# eth.net
KiCad netlist of a schematic drawn in Altium Designer
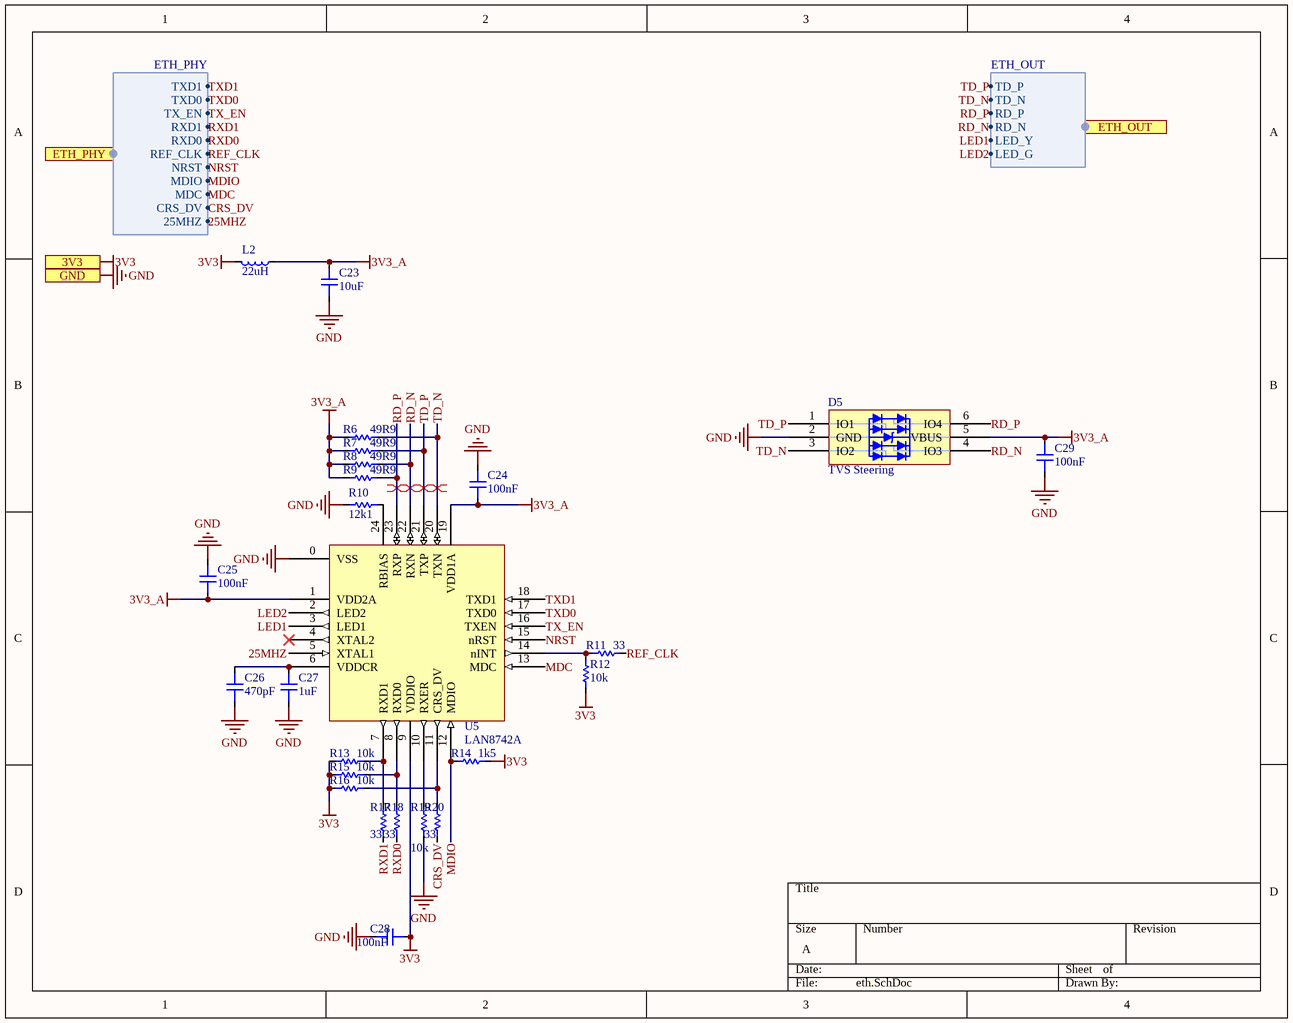
[diagram p0: eth.SchDoc]

(export (version "E")
  (design (tool "Eeschema 10.0.6"))
  (components
    (comp (ref "C23")
      (value "10uF")
      (footprint "CAP 0805 L")
      (description "CAP 0805")
      (libsource (lib "streetbot") (part "CAP 0805"))
    )
    (comp (ref "C24")
      (value "100nF")
      (footprint "CAP 0805 L")
      (description "CAP 0805")
      (libsource (lib "streetbot") (part "CAP 0805"))
    )
    (comp (ref "C25")
      (value "100nF")
      (footprint "CAP 0805 L")
      (description "CAP 0805")
      (libsource (lib "streetbot") (part "CAP 0805"))
    )
    (comp (ref "C26")
      (value "470pF")
      (footprint "CAP 0805 L")
      (description "CAP 0805")
      (libsource (lib "streetbot") (part "CAP 0805"))
    )
    (comp (ref "C27")
      (value "1uF")
      (footprint "CAP 0805 L")
      (description "CAP 0805")
      (libsource (lib "streetbot") (part "CAP 0805"))
    )
    (comp (ref "C28")
      (value "100nF")
      (footprint "CAP 0805 L")
      (description "CAP 0805")
      (libsource (lib "streetbot") (part "CAP 0805"))
    )
    (comp (ref "C29")
      (value "100nF")
      (footprint "CAP 0805 L")
      (description "CAP 0805")
      (libsource (lib "streetbot") (part "CAP 0805"))
    )
    (comp (ref "D5")
      (value "TVS Steering")
      (footprint "SC-74")
      (description "CM1293A-04SO")
      (libsource (lib "streetbot") (part "DTVS 2Rail 4x"))
    )
    (comp (ref "L2")
      (value "22uH")
      (footprint "IND 0805 L")
      (description "IND 0805")
      (libsource (lib "streetbot") (part "IND 0805"))
    )
    (comp (ref "R6")
      (value "49R9")
      (footprint "RES 0603 L")
      (description "RES 0603")
      (libsource (lib "streetbot") (part "RES 0603"))
    )
    (comp (ref "R7")
      (value "49R9")
      (footprint "RES 0603 L")
      (description "RES 0603")
      (libsource (lib "streetbot") (part "RES 0603"))
    )
    (comp (ref "R8")
      (value "49R9")
      (footprint "RES 0603 L")
      (description "RES 0603")
      (libsource (lib "streetbot") (part "RES 0603"))
    )
    (comp (ref "R9")
      (value "49R9")
      (footprint "RES 0603 L")
      (description "RES 0603")
      (libsource (lib "streetbot") (part "RES 0603"))
    )
    (comp (ref "R10")
      (value "12k1")
      (footprint "RES 0603 L")
      (description "RES 0603")
      (libsource (lib "streetbot") (part "RES 0603"))
    )
    (comp (ref "R11")
      (value "33")
      (footprint "RES 0603 L")
      (description "RES 0603")
      (libsource (lib "streetbot") (part "RES 0603"))
    )
    (comp (ref "R12")
      (value "10k")
      (footprint "RES 0603 L")
      (description "RES 0603")
      (libsource (lib "streetbot") (part "RES 0603"))
    )
    (comp (ref "R13")
      (value "10k")
      (footprint "RES 0603 L")
      (description "RES 0603")
      (libsource (lib "streetbot") (part "RES 0603"))
    )
    (comp (ref "R14")
      (value "1k5")
      (footprint "RES 0603 L")
      (description "RES 0603")
      (libsource (lib "streetbot") (part "RES 0603"))
    )
    (comp (ref "R15")
      (value "10k")
      (footprint "RES 0603 L")
      (description "RES 0603")
      (libsource (lib "streetbot") (part "RES 0603"))
    )
    (comp (ref "R16")
      (value "10k")
      (footprint "RES 0603 L")
      (description "RES 0603")
      (libsource (lib "streetbot") (part "RES 0603"))
    )
    (comp (ref "R17")
      (value "33")
      (footprint "RES 0603 L")
      (description "RES 0603")
      (libsource (lib "streetbot") (part "RES 0603"))
    )
    (comp (ref "R18")
      (value "33")
      (footprint "RES 0603 L")
      (description "RES 0603")
      (libsource (lib "streetbot") (part "RES 0603"))
    )
    (comp (ref "R19")
      (value "10k")
      (footprint "RES 0603 L")
      (description "RES 0603")
      (libsource (lib "streetbot") (part "RES 0603"))
    )
    (comp (ref "R20")
      (value "33")
      (footprint "RES 0603 L")
      (description "RES 0603")
      (libsource (lib "streetbot") (part "RES 0603"))
    )
    (comp (ref "U5")
      (value "LAN8742A")
      (footprint "VQFN24")
      (description "LAN8742A-CZ-TR\r\nLAN8742AI-CZ-TR")
      (libsource (lib "streetbot") (part "IC ETH PHY RMII"))
    )
  )
  (nets
    (net (code "3") (name "/25MHZ") (class "Default")
      (node (ref "U5") (pin "5") (pinfunction "XTAL1_5") (pintype "input"))
    )
    (net (code "4") (name "/CRS_DV") (class "Default")
      (node (ref "R20") (pin "1") (pinfunction "1_1") (pintype "passive"))
    )
    (net (code "5") (name "/LED1") (class "Default")
      (node (ref "U5") (pin "3") (pinfunction "LED1_3") (pintype "output"))
    )
    (net (code "6") (name "/LED2") (class "Default")
      (node (ref "U5") (pin "2") (pinfunction "LED2_2") (pintype "output"))
    )
    (net (code "7") (name "/MDC") (class "Default")
      (node (ref "U5") (pin "13") (pinfunction "MDC_13") (pintype "input"))
    )
    (net (code "8") (name "/MDIO") (class "Default")
      (node (ref "R14") (pin "2") (pinfunction "2_2") (pintype "passive"))
      (node (ref "U5") (pin "12") (pinfunction "MDIO_12") (pintype "input"))
    )
    (net (code "9") (name "/NRST") (class "Default")
      (node (ref "U5") (pin "15") (pinfunction "nRST_15") (pintype "input"))
    )
    (net (code "10") (name "/RD_N") (class "Default")
      (node (ref "D5") (pin "4") (pinfunction "IO3_4") (pintype "passive"))
      (node (ref "R8") (pin "1") (pinfunction "1_1") (pintype "passive"))
      (node (ref "U5") (pin "22") (pinfunction "RXN_22") (pintype "bidirectional"))
    )
    (net (code "11") (name "/RD_P") (class "Default")
      (node (ref "D5") (pin "6") (pinfunction "IO4_6") (pintype "passive"))
      (node (ref "R9") (pin "1") (pinfunction "1_1") (pintype "passive"))
      (node (ref "U5") (pin "23") (pinfunction "RXP_23") (pintype "bidirectional"))
    )
    (net (code "12") (name "/REF_CLK") (class "Default")
      (node (ref "R11") (pin "1") (pinfunction "1_1") (pintype "passive"))
    )
    (net (code "13") (name "/RXD0") (class "Default")
      (node (ref "R18") (pin "1") (pinfunction "1_1") (pintype "passive"))
    )
    (net (code "14") (name "/RXD1") (class "Default")
      (node (ref "R17") (pin "1") (pinfunction "1_1") (pintype "passive"))
    )
    (net (code "15") (name "/TD_N") (class "Default")
      (node (ref "D5") (pin "3") (pinfunction "IO2_3") (pintype "passive"))
      (node (ref "R6") (pin "1") (pinfunction "1_1") (pintype "passive"))
      (node (ref "U5") (pin "20") (pinfunction "TXN_20") (pintype "bidirectional"))
    )
    (net (code "16") (name "/TD_P") (class "Default")
      (node (ref "D5") (pin "1") (pinfunction "IO1_1") (pintype "passive"))
      (node (ref "R7") (pin "1") (pinfunction "1_1") (pintype "passive"))
      (node (ref "U5") (pin "21") (pinfunction "TXP_21") (pintype "bidirectional"))
    )
    (net (code "17") (name "/TXD0") (class "Default")
      (node (ref "U5") (pin "17") (pinfunction "TXD0_17") (pintype "input"))
    )
    (net (code "18") (name "/TXD1") (class "Default")
      (node (ref "U5") (pin "18") (pinfunction "TXD1_18") (pintype "input"))
    )
    (net (code "19") (name "/TX_EN") (class "Default")
      (node (ref "U5") (pin "16") (pinfunction "TXEN_16") (pintype "input"))
    )
    (net (code "22") (name "3V3") (class "Default")
      (node (ref "C28") (pin "2") (pinfunction "2_2") (pintype "passive"))
      (node (ref "L2") (pin "2") (pinfunction "2_2") (pintype "passive"))
      (node (ref "R12") (pin "2") (pinfunction "2_2") (pintype "passive"))
      (node (ref "R13") (pin "2") (pinfunction "2_2") (pintype "passive"))
      (node (ref "R14") (pin "1") (pinfunction "1_1") (pintype "passive"))
      (node (ref "R15") (pin "2") (pinfunction "2_2") (pintype "passive"))
      (node (ref "R16") (pin "2") (pinfunction "2_2") (pintype "passive"))
      (node (ref "U5") (pin "9") (pinfunction "VDDIO_9") (pintype "power_in"))
    )
    (net (code "23") (name "3V3_A") (class "Default")
      (node (ref "C23") (pin "2") (pinfunction "2_2") (pintype "passive"))
      (node (ref "C24") (pin "1") (pinfunction "1_1") (pintype "passive"))
      (node (ref "C25") (pin "1") (pinfunction "1_1") (pintype "passive"))
      (node (ref "C29") (pin "2") (pinfunction "2_2") (pintype "passive"))
      (node (ref "D5") (pin "5") (pinfunction "VBUS_5") (pintype "passive"))
      (node (ref "L2") (pin "1") (pinfunction "1_1") (pintype "passive"))
      (node (ref "R6") (pin "2") (pinfunction "2_2") (pintype "passive"))
      (node (ref "R7") (pin "2") (pinfunction "2_2") (pintype "passive"))
      (node (ref "R8") (pin "2") (pinfunction "2_2") (pintype "passive"))
      (node (ref "R9") (pin "2") (pinfunction "2_2") (pintype "passive"))
      (node (ref "U5") (pin "1") (pinfunction "VDD2A_1") (pintype "power_in"))
      (node (ref "U5") (pin "19") (pinfunction "VDD1A_19") (pintype "power_in"))
    )
    (net (code "24") (name "GND") (class "Default")
      (node (ref "C23") (pin "1") (pinfunction "1_1") (pintype "passive"))
      (node (ref "C24") (pin "2") (pinfunction "2_2") (pintype "passive"))
      (node (ref "C25") (pin "2") (pinfunction "2_2") (pintype "passive"))
      (node (ref "C26") (pin "1") (pinfunction "1_1") (pintype "passive"))
      (node (ref "C27") (pin "1") (pinfunction "1_1") (pintype "passive"))
      (node (ref "C28") (pin "1") (pinfunction "1_1") (pintype "passive"))
      (node (ref "C29") (pin "1") (pinfunction "1_1") (pintype "passive"))
      (node (ref "D5") (pin "2") (pinfunction "GND_2") (pintype "passive"))
      (node (ref "R10") (pin "1") (pinfunction "1_1") (pintype "passive"))
      (node (ref "R19") (pin "1") (pinfunction "1_1") (pintype "passive"))
      (node (ref "U5") (pin "0") (pinfunction "VSS_0") (pintype "power_in"))
    )
    (net (code "25") (name "Net-(U5-CRS_DV)") (class "Default")
      (node (ref "R16") (pin "1") (pinfunction "1_1") (pintype "passive"))
      (node (ref "R20") (pin "2") (pinfunction "2_2") (pintype "passive"))
      (node (ref "U5") (pin "11") (pinfunction "CRS_DV_11") (pintype "output"))
    )
    (net (code "26") (name "Net-(U5-RBIAS)") (class "Default")
      (node (ref "R10") (pin "2") (pinfunction "2_2") (pintype "passive"))
      (node (ref "U5") (pin "24") (pinfunction "RBIAS_24") (pintype "passive"))
    )
    (net (code "27") (name "Net-(U5-RXD0)") (class "Default")
      (node (ref "R15") (pin "1") (pinfunction "1_1") (pintype "passive"))
      (node (ref "R18") (pin "2") (pinfunction "2_2") (pintype "passive"))
      (node (ref "U5") (pin "8") (pinfunction "RXD0_8") (pintype "output"))
    )
    (net (code "28") (name "Net-(U5-RXD1)") (class "Default")
      (node (ref "R13") (pin "1") (pinfunction "1_1") (pintype "passive"))
      (node (ref "R17") (pin "2") (pinfunction "2_2") (pintype "passive"))
      (node (ref "U5") (pin "7") (pinfunction "RXD1_7") (pintype "output"))
    )
    (net (code "29") (name "Net-(U5-RXER)") (class "Default")
      (node (ref "R19") (pin "2") (pinfunction "2_2") (pintype "passive"))
      (node (ref "U5") (pin "10") (pinfunction "RXER_10") (pintype "output"))
    )
    (net (code "30") (name "Net-(U5-VDDCR)") (class "Default")
      (node (ref "C26") (pin "2") (pinfunction "2_2") (pintype "passive"))
      (node (ref "C27") (pin "2") (pinfunction "2_2") (pintype "passive"))
      (node (ref "U5") (pin "6") (pinfunction "VDDCR_6") (pintype "power_in"))
    )
    (net (code "31") (name "Net-(U5-nINT)") (class "Default")
      (node (ref "R11") (pin "2") (pinfunction "2_2") (pintype "passive"))
      (node (ref "R12") (pin "1") (pinfunction "1_1") (pintype "passive"))
      (node (ref "U5") (pin "14") (pinfunction "nINT_14") (pintype "output"))
    )
    (net (code "32") (name "unconnected-(U5-XTAL2-Pad4)") (class "Default")
      (node (ref "U5") (pin "4") (pinfunction "XTAL2_4") (pintype "output+no_connect"))
    )
  )
)
